# PA_F.net
KiCad netlist of a schematic drawn in Altium Designer
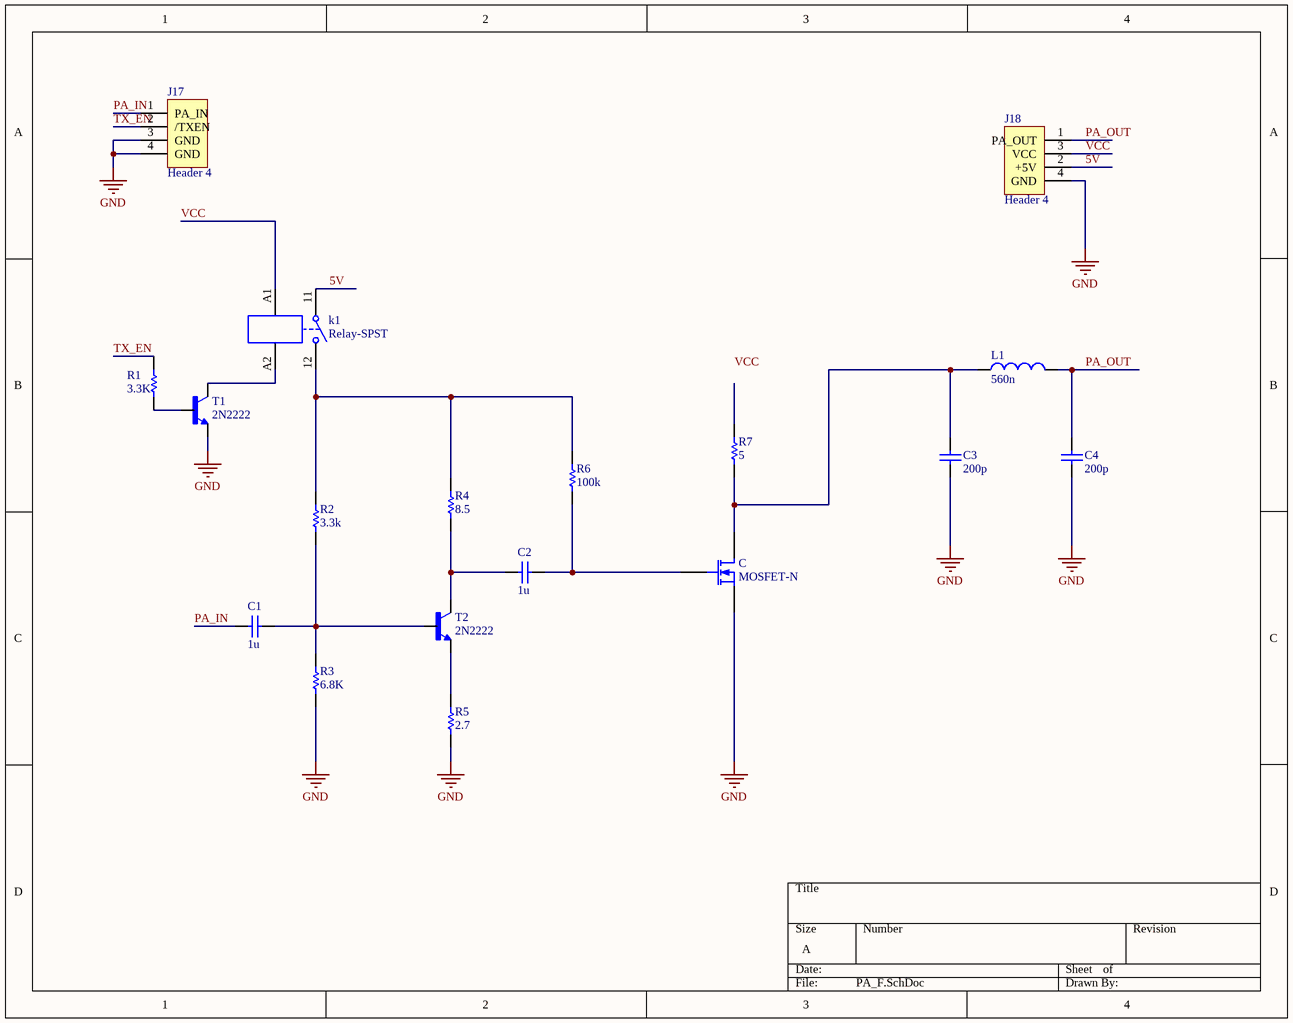
[diagram p0: PA_F.SchDoc]

(export (version "E")
  (design (tool "Eeschema 10.0.6"))
  (components
    (comp (ref "C")
      (value "MOSFET-N")
      (footprint "TO254P1067X483X3124-3P")
      (description "IRF510PBF N-channel MOSFET Transistor; 5.6 A; 100 V; 3-Pin TO-220AB")
      (fields
        (field (name "MANUFACTURER") "Vishay")
        (field (name "MANUFACTURER PART NUMBER") "IRF510PBF")
        (field (name "PUBLISHER") "Altium Limited")
      )
      (libsource (lib "Miscellaneous Devices") (part "MOSFET-N"))
    )
    (comp (ref "C1")
      (value "1u")
      (footprint "RAD-0.1")
      (description "Alum. Electrolytic Cap 1µF 50V 5mm Radial WCAP-ATG5 Series Lifetime 2000h +105°C")
      (fields
        (field (name "MANUFACTURER") "CDE Illinois Capacitor")
        (field (name "MANUFACTURER PART NUMBER") "109CKS016M")
      )
      (libsource (lib "Simulation Generic Components") (part "Capacitor"))
    )
    (comp (ref "C2")
      (value "1u")
      (footprint "RAD-0.1")
      (description "Alum. Electrolytic Cap 1µF 50V 5mm Radial WCAP-ATG5 Series Lifetime 2000h +105°C")
      (fields
        (field (name "MANUFACTURER") "Wurth Electronics")
        (field (name "MANUFACTURER PART NUMBER") "860020672005")
      )
      (libsource (lib "Simulation Generic Components") (part "Capacitor"))
    )
    (comp (ref "C3")
      (value "200p")
      (footprint "rad-0.1")
      (description "Capacitor Multi-layer Ceramic 200pF 5% 250V 2-Pin Through Hole Bulk")
      (fields
        (field (name "MANUFACTURER") "KEMET")
        (field (name "MANUFACTURER PART NUMBER") "C326C201JAG5TA")
      )
      (libsource (lib "Simulation Generic Components") (part "Capacitor"))
    )
    (comp (ref "C4")
      (value "200p")
      (footprint "rad-0.1")
      (description "Capacitor Multi-layer Ceramic 200pF 5% 250V 2-Pin Through Hole Bulk")
      (fields
        (field (name "MANUFACTURER") "KEMET")
        (field (name "MANUFACTURER PART NUMBER") "C326C201JAG5TA")
      )
      (libsource (lib "Simulation Generic Components") (part "Capacitor"))
    )
    (comp (ref "J17")
      (value "Header 4")
      (footprint "HDR1X4")
      (description "Header, 4-Pin")
      (fields (field (name "PUBLISHER") "Altium Limited"))
      (libsource (lib "Miscellaneous Connectors") (part "Header 4"))
    )
    (comp (ref "J18")
      (value "Header 4")
      (footprint "HDR1X4")
      (description "Header, 4-Pin")
      (fields (field (name "PUBLISHER") "Altium Limited"))
      (libsource (lib "") (part "Header 4_1"))
    )
    (comp (ref "k1")
      (value "Relay-SPST")
      (footprint "PCBComponent_1")
      (description "Single-Pole Single-Throw Relay")
      (fields (field (name "PUBLISHER") "Altium Limited"))
      (libsource (lib "Miscellaneous Devices") (part "Relay-SPST"))
    )
    (comp (ref "L1")
      (value "560n")
      (footprint "AXIAL-0.4")
      (description "Inductor")
      (libsource (lib "Simulation Generic Components") (part "Inductor"))
    )
    (comp (ref "R1")
      (value "3.3K")
      (footprint "AXIAL-0.4")
      (description "Res Wirewound 3K Ohm 5% 5W ±30ppm/°C Ceramic Hi Temp Sil AXL Thru-Hole Bulk")
      (fields
        (field (name "MANUFACTURER") "Vishay BCcomponents")
        (field (name "MANUFACTURER PART NUMBER") "MBA02040C3001FC100")
      )
      (libsource (lib "Simulation Generic Components") (part "Resistor"))
    )
    (comp (ref "R2")
      (value "3.3k")
      (footprint "AXIAL-0.4")
      (description "Res Wirewound 3K Ohm 5% 5W ±30ppm/°C Ceramic Hi Temp Sil AXL Thru-Hole Bulk")
      (fields
        (field (name "MANUFACTURER") "Vishay BCcomponents")
        (field (name "MANUFACTURER PART NUMBER") "MBA02040C3001FC100")
      )
      (libsource (lib "Simulation Generic Components") (part "Resistor"))
    )
    (comp (ref "R3")
      (value "6.8K")
      (footprint "AXIAL-0.4")
      (description "Res Wirewound 3K Ohm 5% 5W ±30ppm/°C Ceramic Hi Temp Sil AXL Thru-Hole Bulk")
      (fields
        (field (name "MANUFACTURER") "Vishay BCcomponents")
        (field (name "MANUFACTURER PART NUMBER") "MBA02040C3001FC100")
      )
      (libsource (lib "Simulation Generic Components") (part "Resistor"))
    )
    (comp (ref "R4")
      (value "8.5")
      (footprint "AXIAL-0.4")
      (description "Resistor; Wirewound; Res 33 Ohms; Pwr-Rtg 5 W; Tol 1%; Axial; Silicone-Ceramic")
      (fields
        (field (name "MANUFACTURER") "Piher")
        (field (name "MANUFACTURER PART NUMBER") "N6S25T0C-504-3030")
      )
      (libsource (lib "Simulation Generic Components") (part "Resistor"))
    )
    (comp (ref "R5")
      (value "2.7")
      (footprint "AXIAL-0.4")
      (description "Res Metal Film 1.5 Ohm 5% 3W ±300ppm/°C Conformal AXL Thru-Hole")
      (fields
        (field (name "MANUFACTURER") "Vishay Dale")
        (field (name "MANUFACTURER PART NUMBER") "RN70C2700BB14")
      )
      (libsource (lib "Simulation Generic Components") (part "Resistor"))
    )
    (comp (ref "R6")
      (value "100k")
      (footprint "AXIAL-0.4")
      (description "Resistor, Wirewound, Res 4 Kilohms, Pwr-Rtg 5 W, Tol 5%, Axial, Vitreous Enamel")
      (fields
        (field (name "MANUFACTURER") "Piher")
        (field (name "MANUFACTURER PART NUMBER") "N6S25T0C-504-3030")
      )
      (libsource (lib "Simulation Generic Components") (part "Resistor"))
    )
    (comp (ref "R7")
      (value "5")
      (footprint "AXIAL-0.4")
      (description "Resistor; Wirewound; Res 33 Ohms; Pwr-Rtg 5 W; Tol 1%; Axial; Silicone-Ceramic")
      (fields
        (field (name "MANUFACTURER") "Piher")
        (field (name "MANUFACTURER PART NUMBER") "N6S25T0C-504-3030")
      )
      (libsource (lib "Simulation Generic Components") (part "Resistor"))
    )
    (comp (ref "T1")
      (value "2N2222")
      (footprint "TO92-EBC-OVAL")
      (description "Bipolar (BJT) Transistor NPN 40V 800mA 300MHz 500mW Through Hole TO-18")
      (fields (field (name "MF") "ON Semiconductor"))
      (libsource (lib "2N2222 (2)") (part "2N2222"))
    )
    (comp (ref "T2")
      (value "2N2222")
      (footprint "TO92-EBC-OVAL")
      (description "Bipolar (BJT) Transistor NPN 40V 800mA 300MHz 500mW Through Hole TO-18")
      (fields (field (name "MF") "ON Semiconductor"))
      (libsource (lib "2N2222 (2)") (part "2N2222"))
    )
  )
  (nets
    (net (code "1") (name "/5V") (class "Default")
      (node (ref "J18") (pin "2") (pinfunction "+5V_2") (pintype "passive"))
      (node (ref "k1") (pin "11") (pinfunction "SW1_11") (pintype "passive"))
    )
    (net (code "2") (name "/PA_IN") (class "Default")
      (node (ref "C1") (pin "1") (pinfunction "1_1") (pintype "passive"))
      (node (ref "J17") (pin "1") (pinfunction "PA_IN_1") (pintype "passive"))
    )
    (net (code "3") (name "/PA_OUT") (class "Default")
      (node (ref "C4") (pin "2") (pinfunction "2_2") (pintype "passive"))
      (node (ref "J18") (pin "1") (pinfunction "PA_OUT_1") (pintype "passive"))
      (node (ref "L1") (pin "2") (pinfunction "2_2") (pintype "passive"))
    )
    (net (code "4") (name "/TX_EN") (class "Default")
      (node (ref "J17") (pin "2") (pinfunction "/TXEN_2") (pintype "passive"))
      (node (ref "R1") (pin "2") (pinfunction "2_2") (pintype "passive"))
    )
    (net (code "5") (name "/VCC") (class "Default")
      (node (ref "J18") (pin "3") (pinfunction "VCC_3") (pintype "passive"))
      (node (ref "k1") (pin "A1") (pinfunction "Coil1_A1") (pintype "passive"))
    )
    (net (code "6") (name "GND") (class "Default")
      (node (ref "C") (pin "3") (pinfunction "S_3") (pintype "passive"))
      (node (ref "C3") (pin "1") (pinfunction "1_1") (pintype "passive"))
      (node (ref "C4") (pin "1") (pinfunction "1_1") (pintype "passive"))
      (node (ref "J17") (pin "3") (pinfunction "GND_3") (pintype "passive"))
      (node (ref "J17") (pin "4") (pinfunction "GND_4") (pintype "passive"))
      (node (ref "J18") (pin "4") (pinfunction "GND_4") (pintype "passive"))
      (node (ref "R3") (pin "1") (pinfunction "1_1") (pintype "passive"))
      (node (ref "R5") (pin "1") (pinfunction "1_1") (pintype "passive"))
      (node (ref "T1") (pin "E") (pinfunction "E_E") (pintype "passive"))
    )
    (net (code "7") (name "Net-(C-D)") (class "Default")
      (node (ref "C") (pin "1") (pinfunction "D_1") (pintype "passive"))
      (node (ref "C2") (pin "2") (pinfunction "2_2") (pintype "passive"))
      (node (ref "R6") (pin "1") (pinfunction "1_1") (pintype "passive"))
    )
    (net (code "8") (name "Net-(C-G)") (class "Default")
      (node (ref "C") (pin "2") (pinfunction "G_2") (pintype "passive"))
      (node (ref "C3") (pin "2") (pinfunction "2_2") (pintype "passive"))
      (node (ref "L1") (pin "1") (pinfunction "1_1") (pintype "passive"))
      (node (ref "R7") (pin "1") (pinfunction "1_1") (pintype "passive"))
    )
    (net (code "9") (name "Net-(C1-Pad2)") (class "Default")
      (node (ref "C1") (pin "2") (pinfunction "2_2") (pintype "passive"))
      (node (ref "R2") (pin "1") (pinfunction "1_1") (pintype "passive"))
      (node (ref "R3") (pin "2") (pinfunction "2_2") (pintype "passive"))
      (node (ref "T2") (pin "B") (pinfunction "B_B") (pintype "passive"))
    )
    (net (code "10") (name "Net-(C2-Pad1)") (class "Default")
      (node (ref "C2") (pin "1") (pinfunction "1_1") (pintype "passive"))
      (node (ref "R4") (pin "1") (pinfunction "1_1") (pintype "passive"))
      (node (ref "T2") (pin "C") (pinfunction "C_C") (pintype "passive"))
    )
    (net (code "11") (name "Net-(R1-Pad1)") (class "Default")
      (node (ref "R1") (pin "1") (pinfunction "1_1") (pintype "passive"))
      (node (ref "T1") (pin "B") (pinfunction "B_B") (pintype "passive"))
    )
    (net (code "12") (name "Net-(R5-Pad2)") (class "Default")
      (node (ref "R5") (pin "2") (pinfunction "2_2") (pintype "passive"))
      (node (ref "T2") (pin "E") (pinfunction "E_E") (pintype "passive"))
    )
    (net (code "13") (name "Net-(k1-Coil2)") (class "Default")
      (node (ref "T1") (pin "C") (pinfunction "C_C") (pintype "passive"))
      (node (ref "k1") (pin "A2") (pinfunction "Coil2_A2") (pintype "passive"))
    )
    (net (code "14") (name "Net-(k1-SW2)") (class "Default")
      (node (ref "R2") (pin "2") (pinfunction "2_2") (pintype "passive"))
      (node (ref "R4") (pin "2") (pinfunction "2_2") (pintype "passive"))
      (node (ref "R6") (pin "2") (pinfunction "2_2") (pintype "passive"))
      (node (ref "k1") (pin "12") (pinfunction "SW2_12") (pintype "passive"))
    )
    (net (code "15") (name "unconnected-(R7-Pad2)") (class "Default")
      (node (ref "R7") (pin "2") (pinfunction "2_2") (pintype "passive"))
    )
  )
)
